# PSoC_Connections.net
KiCad netlist of a schematic drawn in Altium Designer
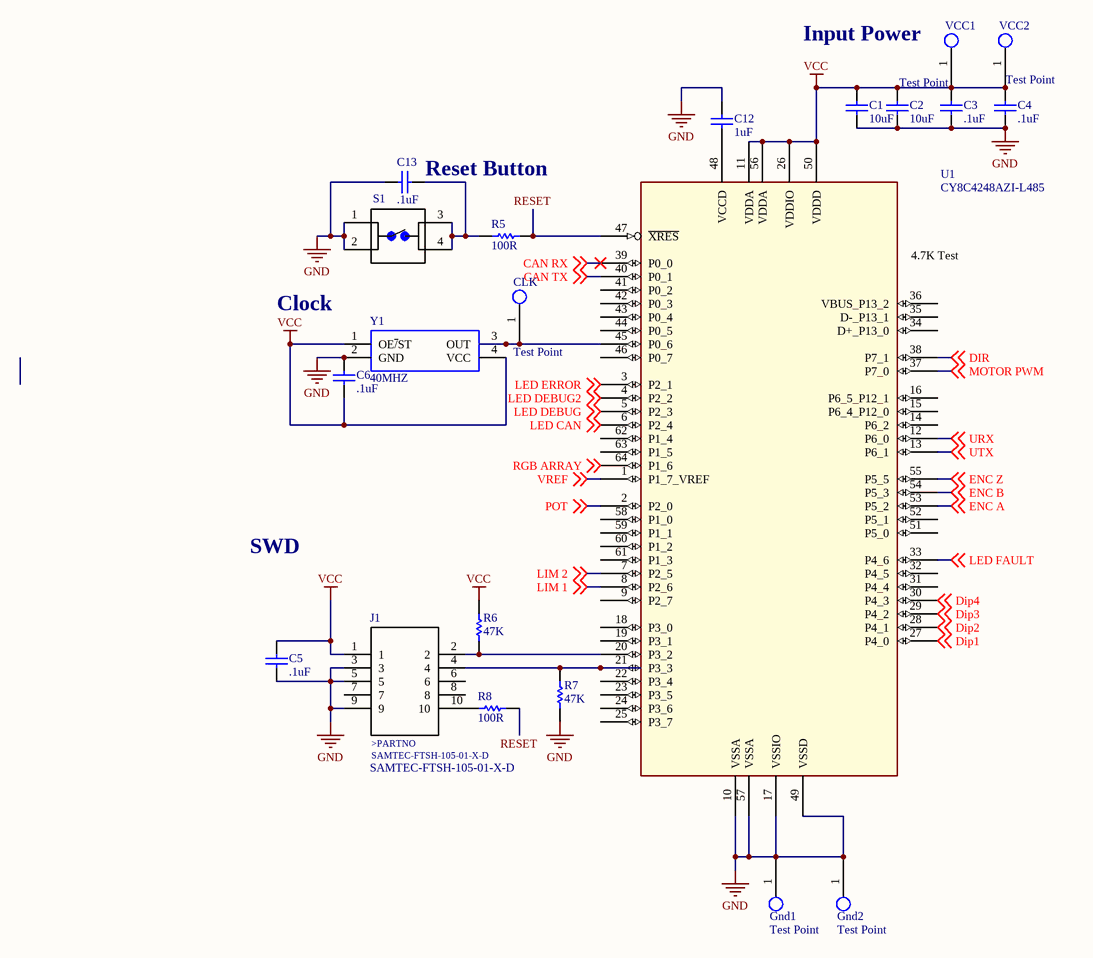
[diagram p0: PSoC Connections.SchDoc]

(export (version "E")
  (design (tool "Eeschema 10.0.6"))
  (components
    (comp (ref "C1")
      (value "10uF")
      (footprint "CAPC0805(2012)130_N")
      (description "CAP 390pF 200V ±5% 0805 (2012 Metric) Thickness 1.3mm SMD")
      (fields (field (name "TOLERANCE") "Â±5%"))
      (libsource (lib "Altium Content Vault") (part "CAP"))
    )
    (comp (ref "C2")
      (value "10uF")
      (footprint "CAPC0805(2012)130_N")
      (description "CAP 390pF 200V ±5% 0805 (2012 Metric) Thickness 1.3mm SMD")
      (fields (field (name "TOLERANCE") "Â±5%"))
      (libsource (lib "Altium Content Vault") (part "CAP"))
    )
    (comp (ref "C3")
      (value ".1uF")
      (footprint "CAPC0805(2012)130_N")
      (description "CAP 390pF 200V ±5% 0805 (2012 Metric) Thickness 1.3mm SMD")
      (fields (field (name "TOLERANCE") "Â±5%"))
      (libsource (lib "Altium Content Vault") (part "CAP"))
    )
    (comp (ref "C4")
      (value ".1uF")
      (footprint "CAPC0805(2012)130_N")
      (description "CAP 390pF 200V ±5% 0805 (2012 Metric) Thickness 1.3mm SMD")
      (fields (field (name "TOLERANCE") "Â±5%"))
      (libsource (lib "Altium Content Vault") (part "CAP"))
    )
    (comp (ref "C5")
      (value ".1uF")
      (footprint "CAPC0805(2012)130_N")
      (description "CAP 390pF 200V ±5% 0805 (2012 Metric) Thickness 1.3mm SMD")
      (fields (field (name "TOLERANCE") "Â±5%"))
      (libsource (lib "Altium Content Vault") (part "CAP"))
    )
    (comp (ref "C6")
      (value ".1uF")
      (footprint "CAPC0805(2012)130_N")
      (description "CAP 390pF 200V ±5% 0805 (2012 Metric) Thickness 1.3mm SMD")
      (fields (field (name "TOLERANCE") "Â±5%"))
      (libsource (lib "Altium Content Vault") (part "CAP"))
    )
    (comp (ref "C12")
      (value "1uF")
      (footprint "CAPC0805(2012)130_N")
      (description "CAP 390pF 200V ±5% 0805 (2012 Metric) Thickness 1.3mm SMD")
      (fields (field (name "TOLERANCE") "Â±5%"))
      (libsource (lib "Altium Content Vault") (part "CAP"))
    )
    (comp (ref "C13")
      (value ".1uF")
      (footprint "CAPC0805(2012)130_N")
      (description "CAP 390pF 200V ±5% 0805 (2012 Metric) Thickness 1.3mm SMD")
      (fields (field (name "TOLERANCE") "Â±5%"))
      (libsource (lib "Altium Content Vault") (part "CAP"))
    )
    (comp (ref "CLK")
      (value "Test Point")
      (footprint "Test Point Through-hole")
      (libsource (lib "Husky Robotics Standard Library 2019-2020") (part "Test Point"))
    )
    (comp (ref "Gnd1")
      (value "Test Point")
      (footprint "Test Point Through-hole")
      (libsource (lib "Husky Robotics Standard Library 2019-2020") (part "Test Point"))
    )
    (comp (ref "Gnd2")
      (value "Test Point")
      (footprint "Test Point Through-hole")
      (libsource (lib "Husky Robotics Standard Library 2019-2020") (part "Test Point"))
    )
    (comp (ref "J1")
      (value "SAMTEC-FTSH-105-01-X-D")
      (footprint "SAMTEC-FTSH-105-01-X-D")
      (libsource (lib "Husky Robotics Standard Library 2019-2020") (part "SAMTEC-FTSH-105-01-X-D"))
    )
    (comp (ref "R5")
      (value "100R")
      (footprint "RESC0805(2012)_N")
      (description "120R 0.125W 5% 0805 (2012 Metric)  SMD")
      (fields (field (name "TOLERANCE") "5 %") (field (name "POWER") "0.125 W"))
      (libsource (lib "Husky Robotics Standard Library 2019-2020") (part "120R 5% 0805"))
    )
    (comp (ref "R6")
      (value "47K")
      (footprint "RESC0805(2012)_N")
      (description "4.7K")
      (fields (field (name "TOLERANCE") "5 %") (field (name "POWER") "0.125 W"))
      (libsource (lib "Husky Robotics Standard Library 2019-2020") (part "120R 5% 0805"))
    )
    (comp (ref "R7")
      (value "47K")
      (footprint "RESC0805(2012)_N")
      (description "120R 0.125W 5% 0805 (2012 Metric)  SMD")
      (fields (field (name "TOLERANCE") "5 %") (field (name "POWER") "0.125 W"))
      (libsource (lib "Husky Robotics Standard Library 2019-2020") (part "120R 5% 0805"))
    )
    (comp (ref "R8")
      (value "100R")
      (footprint "RESC0805(2012)_N")
      (description "120R 0.125W 5% 0805 (2012 Metric)  SMD")
      (fields (field (name "TOLERANCE") "5 %") (field (name "POWER") "0.125 W"))
      (libsource (lib "Husky Robotics Standard Library 2019-2020") (part "120R 5% 0805"))
    )
    (comp (ref "S1")
      (value "1825910-7")
      (footprint "Switch 6mm 24V (NO)")
      (description "FSM4JAH=6MM TACT SWITCH, HIGH TEMP")
      (fields (field (name "MF") "TE Connectivity") (field (name "DIGI-KEY_PART_NUMBER") "450-1804-ND"))
      (libsource (lib "Husky Robotics Standard Library 2019-2020") (part "Switch 6mm 24V (NO)"))
    )
    (comp (ref "U1")
      (value "CY8C4248AZI-L485")
      (footprint "TQFP50P1200X1200X160-64N")
      (libsource (lib "Husky Robotics Standard Library 2019-2020") (part "CY8C4248AZI-L485"))
    )
    (comp (ref "VCC1")
      (value "Test Point")
      (footprint "Test Point Through-hole")
      (libsource (lib "Husky Robotics Standard Library 2019-2020") (part "Test Point"))
    )
    (comp (ref "VCC2")
      (value "Test Point")
      (footprint "Test Point Through-hole")
      (libsource (lib "Husky Robotics Standard Library 2019-2020") (part "Test Point"))
    )
    (comp (ref "Y1")
      (value "40MHZ")
      (footprint "SG-636")
      (description "Standard Clock Oscillators 50MHz 3.3Volt 100ppm -20C +70C")
      (fields (field (name "MANUFACTURER_PART_NUMBER") "SG-636PCW 50.0000MC3: ROHS"))
      (libsource (lib "Husky Robotics Standard Library 2019-2020") (part "SG-636"))
    )
  )
  (nets
    (net (code "1") (name "/RESET") (class "Default")
      (node (ref "R5") (pin "2") (pinfunction "2_2") (pintype "passive"))
      (node (ref "R8") (pin "2") (pinfunction "2_2") (pintype "passive"))
      (node (ref "U1") (pin "47") (pinfunction "~{XRES}_47") (pintype "input"))
    )
    (net (code "2") (name "CAN RX") (class "Default")
      (node (ref "U1") (pin "39") (pinfunction "P0_0_39") (pintype "bidirectional"))
    )
    (net (code "3") (name "CAN TX") (class "Default")
      (node (ref "U1") (pin "40") (pinfunction "P0_1_40") (pintype "bidirectional"))
    )
    (net (code "4") (name "DIR") (class "Default")
      (node (ref "U1") (pin "38") (pinfunction "P7_1_38") (pintype "bidirectional"))
    )
    (net (code "5") (name "Dip1") (class "Default")
      (node (ref "U1") (pin "27") (pinfunction "P4_0_27") (pintype "bidirectional"))
    )
    (net (code "6") (name "Dip2") (class "Default")
      (node (ref "U1") (pin "28") (pinfunction "P4_1_28") (pintype "bidirectional"))
    )
    (net (code "7") (name "Dip3") (class "Default")
      (node (ref "U1") (pin "29") (pinfunction "P4_2_29") (pintype "bidirectional"))
    )
    (net (code "8") (name "Dip4") (class "Default")
      (node (ref "U1") (pin "30") (pinfunction "P4_3_30") (pintype "bidirectional"))
    )
    (net (code "9") (name "ENC A") (class "Default")
      (node (ref "U1") (pin "53") (pinfunction "P5_2_53") (pintype "bidirectional"))
    )
    (net (code "10") (name "ENC B") (class "Default")
      (node (ref "U1") (pin "54") (pinfunction "P5_3_54") (pintype "bidirectional"))
    )
    (net (code "11") (name "ENC Z") (class "Default")
      (node (ref "U1") (pin "55") (pinfunction "P5_5_55") (pintype "bidirectional"))
    )
    (net (code "12") (name "GND") (class "Default")
      (node (ref "C1") (pin "1") (pinfunction "1_1") (pintype "passive"))
      (node (ref "C12") (pin "2") (pinfunction "2_2") (pintype "passive"))
      (node (ref "C13") (pin "2") (pinfunction "2_2") (pintype "passive"))
      (node (ref "C2") (pin "1") (pinfunction "1_1") (pintype "passive"))
      (node (ref "C3") (pin "1") (pinfunction "1_1") (pintype "passive"))
      (node (ref "C4") (pin "1") (pinfunction "1_1") (pintype "passive"))
      (node (ref "C5") (pin "1") (pinfunction "1_1") (pintype "passive"))
      (node (ref "C6") (pin "2") (pinfunction "2_2") (pintype "passive"))
      (node (ref "Gnd1") (pin "1") (pinfunction "1_1") (pintype "passive"))
      (node (ref "Gnd2") (pin "1") (pinfunction "1_1") (pintype "passive"))
      (node (ref "J1") (pin "3") (pinfunction "3_3") (pintype "passive"))
      (node (ref "J1") (pin "5") (pinfunction "5_5") (pintype "passive"))
      (node (ref "J1") (pin "9") (pinfunction "9_9") (pintype "passive"))
      (node (ref "R7") (pin "1") (pinfunction "1_1") (pintype "passive"))
      (node (ref "S1") (pin "1") (pinfunction "1_1") (pintype "passive"))
      (node (ref "S1") (pin "2") (pinfunction "2_2") (pintype "passive"))
      (node (ref "U1") (pin "10") (pinfunction "VSSA_10") (pintype "power_in"))
      (node (ref "U1") (pin "17") (pinfunction "VSSIO_17") (pintype "power_in"))
      (node (ref "U1") (pin "49") (pinfunction "VSSD_49") (pintype "power_in"))
      (node (ref "U1") (pin "57") (pinfunction "VSSA_57") (pintype "power_in"))
      (node (ref "Y1") (pin "2") (pinfunction "GND_2") (pintype "passive"))
    )
    (net (code "13") (name "LED CAN") (class "Default")
      (node (ref "U1") (pin "6") (pinfunction "P2_4_6") (pintype "bidirectional"))
    )
    (net (code "14") (name "LED DEBUG") (class "Default")
      (node (ref "U1") (pin "5") (pinfunction "P2_3_5") (pintype "bidirectional"))
    )
    (net (code "15") (name "LED DEBUG2") (class "Default")
      (node (ref "U1") (pin "4") (pinfunction "P2_2_4") (pintype "bidirectional"))
    )
    (net (code "16") (name "LED ERROR") (class "Default")
      (node (ref "U1") (pin "3") (pinfunction "P2_1_3") (pintype "bidirectional"))
    )
    (net (code "17") (name "LED FAULT") (class "Default")
      (node (ref "U1") (pin "33") (pinfunction "P4_6_33") (pintype "bidirectional"))
    )
    (net (code "18") (name "LIM 1") (class "Default")
      (node (ref "U1") (pin "8") (pinfunction "P2_6_8") (pintype "bidirectional"))
    )
    (net (code "19") (name "LIM 2") (class "Default")
      (node (ref "U1") (pin "7") (pinfunction "P2_5_7") (pintype "bidirectional"))
    )
    (net (code "20") (name "MOTOR PWM") (class "Default")
      (node (ref "U1") (pin "37") (pinfunction "P7_0_37") (pintype "bidirectional"))
    )
    (net (code "21") (name "Net-(C13-Pad1)") (class "Default")
      (node (ref "C13") (pin "1") (pinfunction "1_1") (pintype "passive"))
      (node (ref "R5") (pin "1") (pinfunction "1_1") (pintype "passive"))
      (node (ref "S1") (pin "3") (pinfunction "3_3") (pintype "passive"))
      (node (ref "S1") (pin "4") (pinfunction "4_4") (pintype "passive"))
    )
    (net (code "22") (name "Net-(J1-Pad10)") (class "Default")
      (node (ref "J1") (pin "10") (pinfunction "10_10") (pintype "passive"))
      (node (ref "R8") (pin "1") (pinfunction "1_1") (pintype "passive"))
    )
    (net (code "23") (name "Net-(U1-P0_6)") (class "Default")
      (node (ref "CLK") (pin "1") (pinfunction "1_1") (pintype "passive"))
      (node (ref "U1") (pin "45") (pinfunction "P0_6_45") (pintype "bidirectional"))
      (node (ref "Y1") (pin "3") (pinfunction "OUT_3") (pintype "passive"))
    )
    (net (code "24") (name "Net-(U1-P3_2)") (class "Default")
      (node (ref "J1") (pin "2") (pinfunction "2_2") (pintype "passive"))
      (node (ref "R6") (pin "1") (pinfunction "1_1") (pintype "passive"))
      (node (ref "U1") (pin "20") (pinfunction "P3_2_20") (pintype "bidirectional"))
    )
    (net (code "25") (name "Net-(U1-P3_3)") (class "Default")
      (node (ref "J1") (pin "4") (pinfunction "4_4") (pintype "passive"))
      (node (ref "R7") (pin "2") (pinfunction "2_2") (pintype "passive"))
      (node (ref "U1") (pin "21") (pinfunction "P3_3_21") (pintype "bidirectional"))
    )
    (net (code "26") (name "Net-(U1-VCCD)") (class "Default")
      (node (ref "C12") (pin "1") (pinfunction "1_1") (pintype "passive"))
      (node (ref "U1") (pin "48") (pinfunction "VCCD_48") (pintype "power_in"))
    )
    (net (code "27") (name "POT") (class "Default")
      (node (ref "U1") (pin "2") (pinfunction "P2_0_2") (pintype "bidirectional"))
    )
    (net (code "28") (name "RGB ARRAY") (class "Default")
      (node (ref "U1") (pin "64") (pinfunction "P1_6_64") (pintype "bidirectional"))
    )
    (net (code "29") (name "URX") (class "Default")
      (node (ref "U1") (pin "12") (pinfunction "P6_0_12") (pintype "bidirectional"))
    )
    (net (code "30") (name "UTX") (class "Default")
      (node (ref "U1") (pin "13") (pinfunction "P6_1_13") (pintype "bidirectional"))
    )
    (net (code "31") (name "VCC") (class "Default")
      (node (ref "C1") (pin "2") (pinfunction "2_2") (pintype "passive"))
      (node (ref "C2") (pin "2") (pinfunction "2_2") (pintype "passive"))
      (node (ref "C3") (pin "2") (pinfunction "2_2") (pintype "passive"))
      (node (ref "C4") (pin "2") (pinfunction "2_2") (pintype "passive"))
      (node (ref "C5") (pin "2") (pinfunction "2_2") (pintype "passive"))
      (node (ref "C6") (pin "1") (pinfunction "1_1") (pintype "passive"))
      (node (ref "J1") (pin "1") (pinfunction "1_1") (pintype "passive"))
      (node (ref "R6") (pin "2") (pinfunction "2_2") (pintype "passive"))
      (node (ref "U1") (pin "11") (pinfunction "VDDA_11") (pintype "power_in"))
      (node (ref "U1") (pin "26") (pinfunction "VDDIO_26") (pintype "power_in"))
      (node (ref "U1") (pin "50") (pinfunction "VDDD_50") (pintype "power_in"))
      (node (ref "U1") (pin "56") (pinfunction "VDDA_56") (pintype "power_in"))
      (node (ref "VCC1") (pin "1") (pinfunction "1_1") (pintype "passive"))
      (node (ref "VCC2") (pin "1") (pinfunction "1_1") (pintype "passive"))
      (node (ref "Y1") (pin "1") (pinfunction "OE~{/}ST_1") (pintype "passive"))
      (node (ref "Y1") (pin "4") (pinfunction "VCC_4") (pintype "power_in"))
    )
    (net (code "32") (name "VREF") (class "Default")
      (node (ref "U1") (pin "1") (pinfunction "P1_7_VREF_1") (pintype "bidirectional"))
    )
    (net (code "33") (name "unconnected-(J1-Pad6)") (class "Default")
      (node (ref "J1") (pin "6") (pinfunction "6_6") (pintype "passive"))
    )
    (net (code "34") (name "unconnected-(J1-Pad7)") (class "Default")
      (node (ref "J1") (pin "7") (pinfunction "7_7") (pintype "passive"))
    )
    (net (code "35") (name "unconnected-(J1-Pad8)") (class "Default")
      (node (ref "J1") (pin "8") (pinfunction "8_8") (pintype "passive"))
    )
    (net (code "36") (name "unconnected-(U1-D+_P13_0-Pad34)") (class "Default")
      (node (ref "U1") (pin "34") (pinfunction "D+_P13_0_34") (pintype "bidirectional"))
    )
    (net (code "37") (name "unconnected-(U1-D-_P13_1-Pad35)") (class "Default")
      (node (ref "U1") (pin "35") (pinfunction "D-_P13_1_35") (pintype "bidirectional"))
    )
    (net (code "38") (name "unconnected-(U1-P0_2-Pad41)") (class "Default")
      (node (ref "U1") (pin "41") (pinfunction "P0_2_41") (pintype "bidirectional"))
    )
    (net (code "39") (name "unconnected-(U1-P0_3-Pad42)") (class "Default")
      (node (ref "U1") (pin "42") (pinfunction "P0_3_42") (pintype "bidirectional"))
    )
    (net (code "40") (name "unconnected-(U1-P0_4-Pad43)") (class "Default")
      (node (ref "U1") (pin "43") (pinfunction "P0_4_43") (pintype "bidirectional"))
    )
    (net (code "41") (name "unconnected-(U1-P0_5-Pad44)") (class "Default")
      (node (ref "U1") (pin "44") (pinfunction "P0_5_44") (pintype "bidirectional"))
    )
    (net (code "42") (name "unconnected-(U1-P0_7-Pad46)") (class "Default")
      (node (ref "U1") (pin "46") (pinfunction "P0_7_46") (pintype "bidirectional"))
    )
    (net (code "43") (name "unconnected-(U1-P1_0-Pad58)") (class "Default")
      (node (ref "U1") (pin "58") (pinfunction "P1_0_58") (pintype "bidirectional"))
    )
    (net (code "44") (name "unconnected-(U1-P1_1-Pad59)") (class "Default")
      (node (ref "U1") (pin "59") (pinfunction "P1_1_59") (pintype "bidirectional"))
    )
    (net (code "45") (name "unconnected-(U1-P1_2-Pad60)") (class "Default")
      (node (ref "U1") (pin "60") (pinfunction "P1_2_60") (pintype "bidirectional"))
    )
    (net (code "46") (name "unconnected-(U1-P1_3-Pad61)") (class "Default")
      (node (ref "U1") (pin "61") (pinfunction "P1_3_61") (pintype "bidirectional"))
    )
    (net (code "47") (name "unconnected-(U1-P1_4-Pad62)") (class "Default")
      (node (ref "U1") (pin "62") (pinfunction "P1_4_62") (pintype "bidirectional"))
    )
    (net (code "48") (name "unconnected-(U1-P1_5-Pad63)") (class "Default")
      (node (ref "U1") (pin "63") (pinfunction "P1_5_63") (pintype "bidirectional"))
    )
    (net (code "49") (name "unconnected-(U1-P2_7-Pad9)") (class "Default")
      (node (ref "U1") (pin "9") (pinfunction "P2_7_9") (pintype "bidirectional"))
    )
    (net (code "50") (name "unconnected-(U1-P3_0-Pad18)") (class "Default")
      (node (ref "U1") (pin "18") (pinfunction "P3_0_18") (pintype "bidirectional"))
    )
    (net (code "51") (name "unconnected-(U1-P3_1-Pad19)") (class "Default")
      (node (ref "U1") (pin "19") (pinfunction "P3_1_19") (pintype "bidirectional"))
    )
    (net (code "52") (name "unconnected-(U1-P3_4-Pad22)") (class "Default")
      (node (ref "U1") (pin "22") (pinfunction "P3_4_22") (pintype "bidirectional"))
    )
    (net (code "53") (name "unconnected-(U1-P3_5-Pad23)") (class "Default")
      (node (ref "U1") (pin "23") (pinfunction "P3_5_23") (pintype "bidirectional"))
    )
    (net (code "54") (name "unconnected-(U1-P3_6-Pad24)") (class "Default")
      (node (ref "U1") (pin "24") (pinfunction "P3_6_24") (pintype "bidirectional"))
    )
    (net (code "55") (name "unconnected-(U1-P3_7-Pad25)") (class "Default")
      (node (ref "U1") (pin "25") (pinfunction "P3_7_25") (pintype "bidirectional"))
    )
    (net (code "56") (name "unconnected-(U1-P4_4-Pad31)") (class "Default")
      (node (ref "U1") (pin "31") (pinfunction "P4_4_31") (pintype "bidirectional"))
    )
    (net (code "57") (name "unconnected-(U1-P4_5-Pad32)") (class "Default")
      (node (ref "U1") (pin "32") (pinfunction "P4_5_32") (pintype "bidirectional"))
    )
    (net (code "58") (name "unconnected-(U1-P5_0-Pad51)") (class "Default")
      (node (ref "U1") (pin "51") (pinfunction "P5_0_51") (pintype "bidirectional"))
    )
    (net (code "59") (name "unconnected-(U1-P5_1-Pad52)") (class "Default")
      (node (ref "U1") (pin "52") (pinfunction "P5_1_52") (pintype "bidirectional"))
    )
    (net (code "60") (name "unconnected-(U1-P6_2-Pad14)") (class "Default")
      (node (ref "U1") (pin "14") (pinfunction "P6_2_14") (pintype "bidirectional"))
    )
    (net (code "61") (name "unconnected-(U1-P6_4_P12_0-Pad15)") (class "Default")
      (node (ref "U1") (pin "15") (pinfunction "P6_4_P12_0_15") (pintype "bidirectional"))
    )
    (net (code "62") (name "unconnected-(U1-P6_5_P12_1-Pad16)") (class "Default")
      (node (ref "U1") (pin "16") (pinfunction "P6_5_P12_1_16") (pintype "bidirectional"))
    )
    (net (code "63") (name "unconnected-(U1-VBUS_P13_2-Pad36)") (class "Default")
      (node (ref "U1") (pin "36") (pinfunction "VBUS_P13_2_36") (pintype "bidirectional"))
    )
  )
)
